# oshi-fuse-board-mk-1_tr5.net
KiCad netlist of a schematic drawn in EAGLE
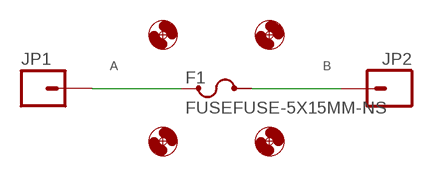
[diagram p0: schematic, sheet 1]

(export (version "E")
  (design (tool "Eeschema 10.0.6"))
  (components
    (comp (ref "F1")
      (value "FUSEFUSE-5X15MM-NS")
      (footprint "eagle-import:FUSE-2AG-NS")
      (libsource (lib "eagle-import") (part "FUSEFUSE-5X15MM-NS"))
    )
    (comp (ref "H1")
      (value "HOLE#2")
      (footprint "eagle-import:HOLE-#2")
      (libsource (lib "eagle-import") (part "HOLE#2"))
    )
    (comp (ref "H2")
      (value "HOLE#2")
      (footprint "eagle-import:HOLE-#2")
      (libsource (lib "eagle-import") (part "HOLE#2"))
    )
    (comp (ref "H3")
      (value "HOLE#2")
      (footprint "eagle-import:HOLE-#2")
      (libsource (lib "eagle-import") (part "HOLE#2"))
    )
    (comp (ref "H4")
      (value "HOLE#2")
      (footprint "eagle-import:HOLE-#2")
      (libsource (lib "eagle-import") (part "HOLE#2"))
    )
    (comp (ref "JP1")
      (value "M01SCREW-IT")
      (footprint "eagle-import:1X01-RING-TERM-6-32")
      (libsource (lib "eagle-import") (part "M01SCREW-IT"))
    )
    (comp (ref "JP2")
      (value "M01SCREW-IT")
      (footprint "eagle-import:1X01-RING-TERM-6-32")
      (libsource (lib "eagle-import") (part "M01SCREW-IT"))
    )
  )
  (nets
    (net (code "1") (name "/A") (class "Default")
      (node (ref "F1") (pin "1") (pinfunction "1_1") (pintype "passive"))
      (node (ref "F1") (pin "1@1") (pinfunction "1_1@1") (pintype "passive"))
      (node (ref "JP1") (pin "P$1") (pinfunction "1_P$1") (pintype "passive"))
      (node (ref "JP1") (pin "P$2") (pinfunction "1_P$2") (pintype "passive"))
      (node (ref "JP1") (pin "P$3") (pinfunction "1_P$3") (pintype "passive"))
      (node (ref "JP1") (pin "P$4") (pinfunction "1_P$4") (pintype "passive"))
      (node (ref "JP1") (pin "P$5") (pinfunction "1_P$5") (pintype "passive"))
    )
    (net (code "2") (name "/B") (class "Default")
      (node (ref "F1") (pin "2") (pinfunction "2_2") (pintype "passive"))
      (node (ref "JP2") (pin "P$1") (pinfunction "1_P$1") (pintype "passive"))
      (node (ref "JP2") (pin "P$2") (pinfunction "1_P$2") (pintype "passive"))
      (node (ref "JP2") (pin "P$3") (pinfunction "1_P$3") (pintype "passive"))
      (node (ref "JP2") (pin "P$4") (pinfunction "1_P$4") (pintype "passive"))
      (node (ref "JP2") (pin "P$5") (pinfunction "1_P$5") (pintype "passive"))
    )
  )
)
